# ADC_SarSol.net
KiCad netlist of a schematic drawn in Altium Designer
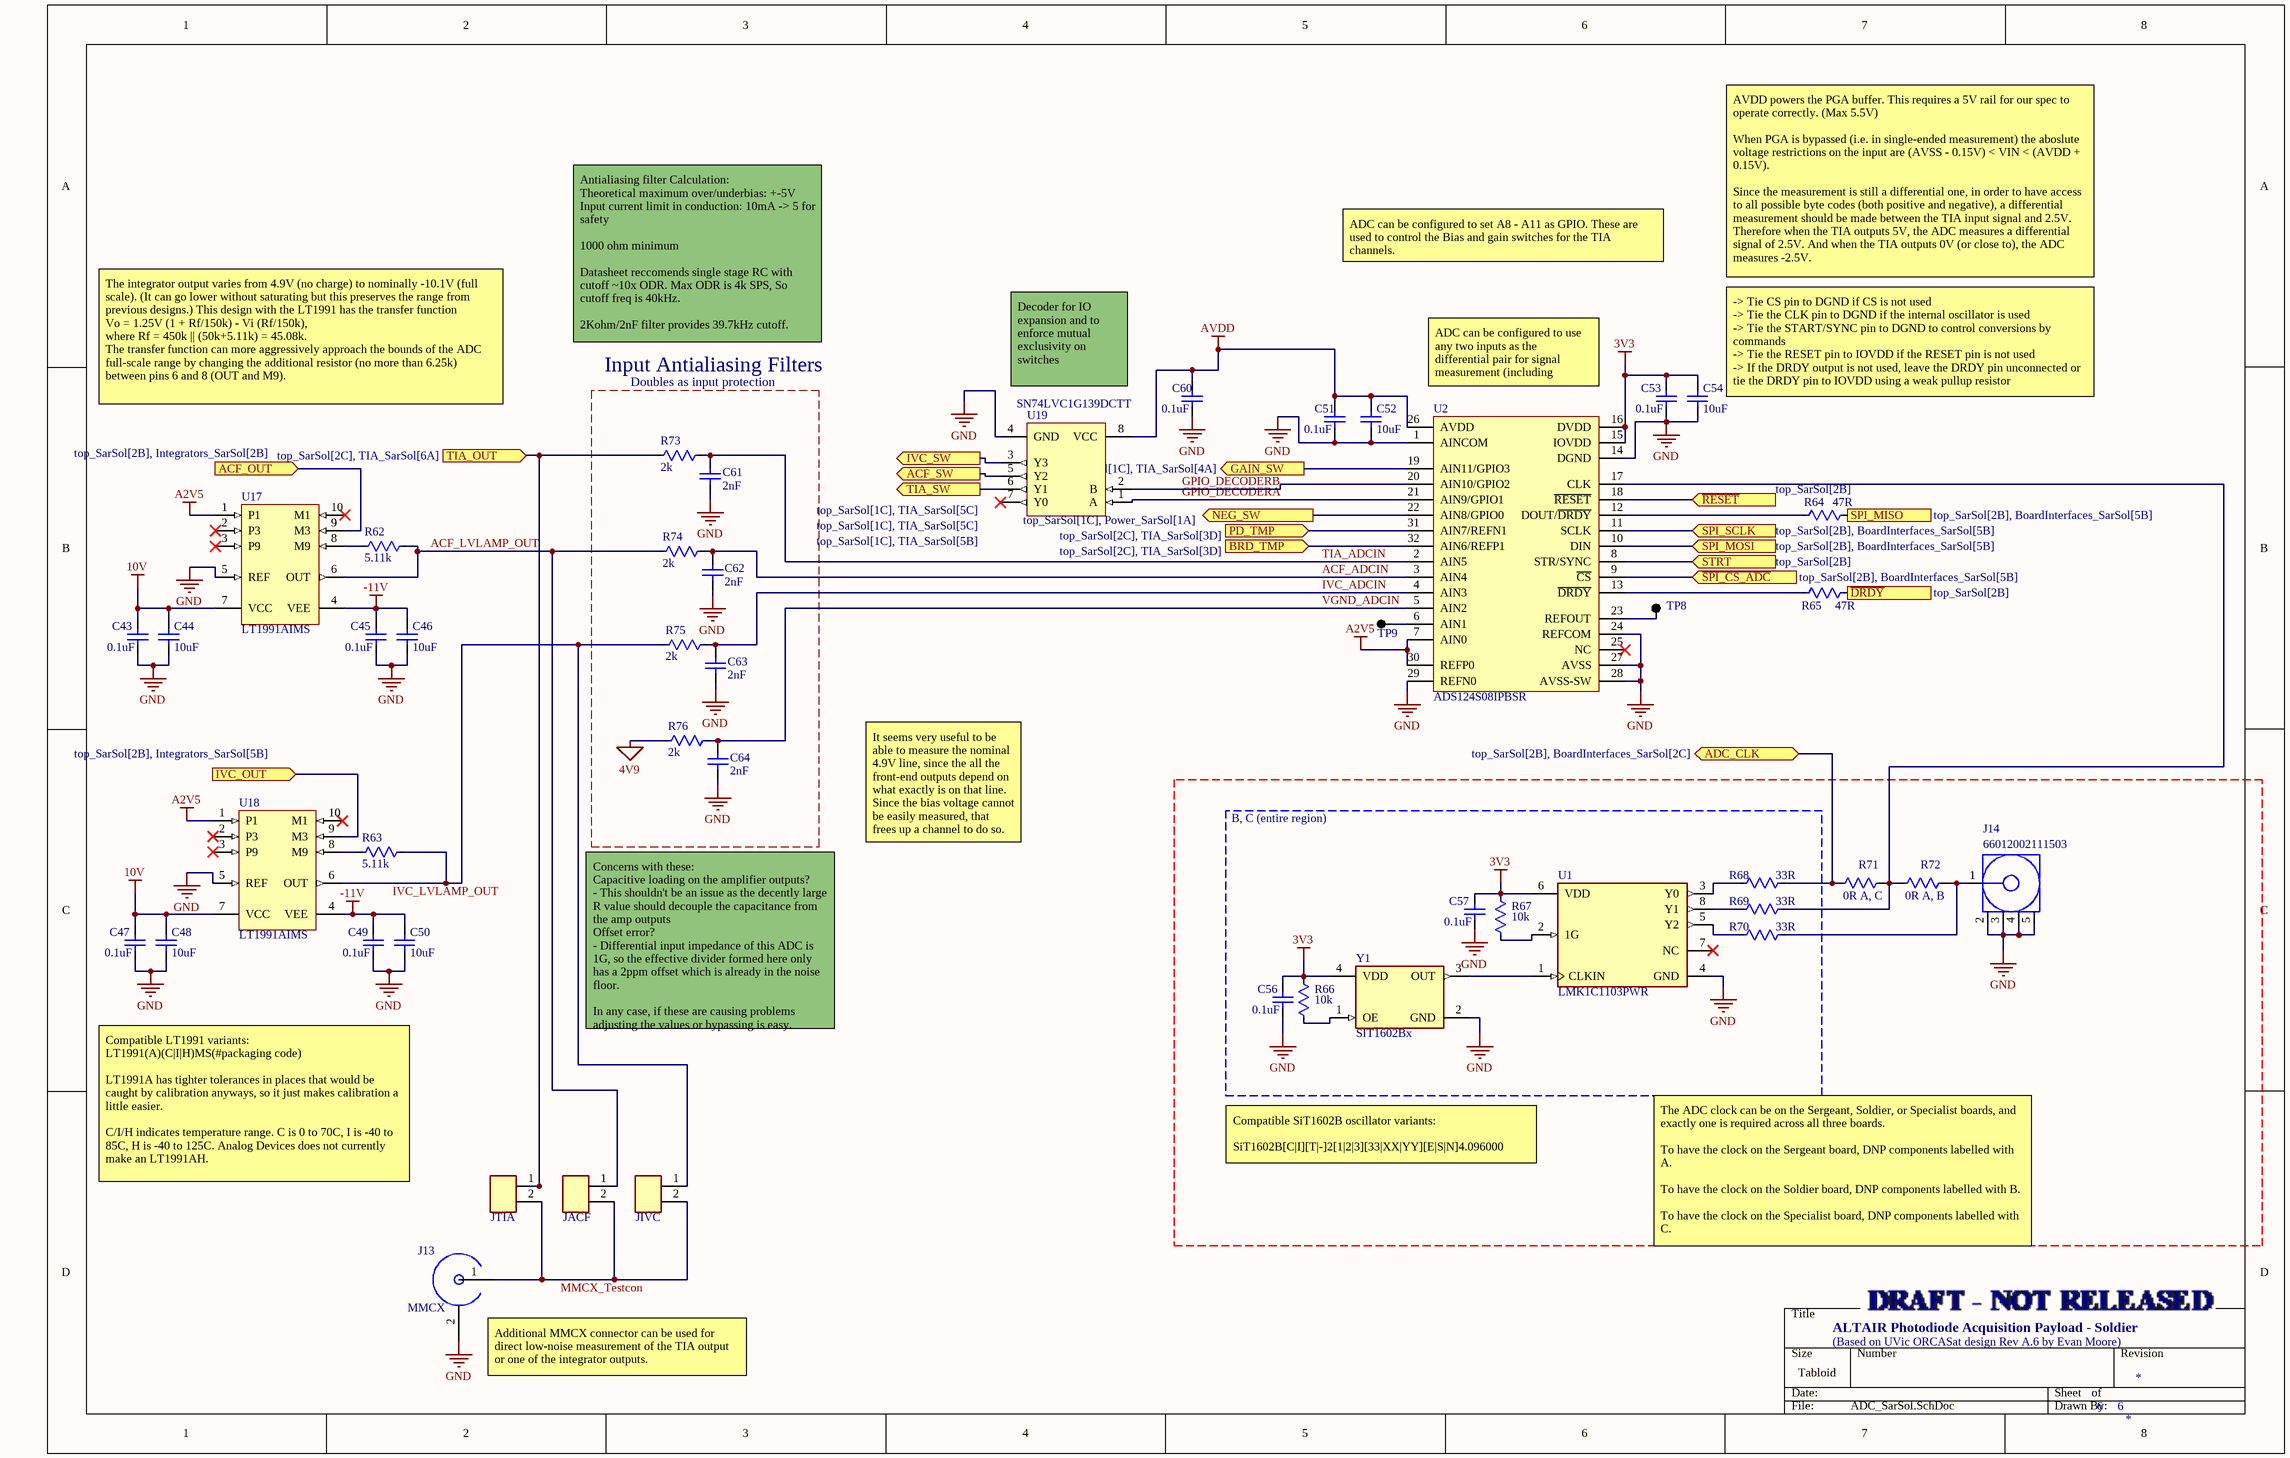
[diagram p0: ADC_SarSol.SchDoc]

(export (version "E")
  (design (tool "Eeschema 10.0.6"))
  (components
    (comp (ref "C43")
      (value "0.1uF")
      (footprint "CAP 0603 NON-IPC KEMET X7R")
      (description "Kemet C0603C104K5RACAUTO - Cap Ceramic 0.1uF 50V X7R 10% 0603 125C Paper T/R")
      (fields (field (name "MF") "Kemet") (field (name "MP") "C0603C104K5RACAUTO"))
      (libsource (lib "ALTAIR_PD_Capacitors") (part "CAP"))
    )
    (comp (ref "C44")
      (value "10uF")
      (footprint "CAP 0805 IPC MID DENSITY")
      (description "Murata GRM21BR61E106KA73L - Cap Ceramic 10uF 10% 25V X5R 0805")
      (fields (field (name "MF") "Murata") (field (name "MP") "GRM21BR61E106KA73L"))
      (libsource (lib "ALTAIR_PD_Capacitors") (part "CAP"))
    )
    (comp (ref "C45")
      (value "0.1uF")
      (footprint "CAP 0603 NON-IPC KEMET X7R")
      (description "Kemet C0603C104K5RACAUTO - Cap Ceramic 0.1uF 50V X7R 10% 0603 125C Paper T/R")
      (fields (field (name "MF") "Kemet") (field (name "MP") "C0603C104K5RACAUTO"))
      (libsource (lib "ALTAIR_PD_Capacitors") (part "CAP"))
    )
    (comp (ref "C46")
      (value "10uF")
      (footprint "CAP 0805 IPC MID DENSITY")
      (description "Murata GRM21BR61E106KA73L - Cap Ceramic 10uF 10% 25V X5R 0805")
      (fields (field (name "MF") "Murata") (field (name "MP") "GRM21BR61E106KA73L"))
      (libsource (lib "ALTAIR_PD_Capacitors") (part "CAP"))
    )
    (comp (ref "C47")
      (value "0.1uF")
      (footprint "CAP 0603 NON-IPC KEMET X7R")
      (description "Kemet C0603C104K5RACAUTO - Cap Ceramic 0.1uF 50V X7R 10% 0603 125C Paper T/R")
      (fields (field (name "MF") "Kemet") (field (name "MP") "C0603C104K5RACAUTO"))
      (libsource (lib "ALTAIR_PD_Capacitors") (part "CAP"))
    )
    (comp (ref "C48")
      (value "10uF")
      (footprint "CAP 0805 IPC MID DENSITY")
      (description "Murata GRM21BR61E106KA73L - Cap Ceramic 10uF 10% 25V X5R 0805")
      (fields (field (name "MF") "Murata") (field (name "MP") "GRM21BR61E106KA73L"))
      (libsource (lib "ALTAIR_PD_Capacitors") (part "CAP"))
    )
    (comp (ref "C49")
      (value "0.1uF")
      (footprint "CAP 0603 NON-IPC KEMET X7R")
      (description "Kemet C0603C104K5RACAUTO - Cap Ceramic 0.1uF 50V X7R 10% 0603 125C Paper T/R")
      (fields (field (name "MF") "Kemet") (field (name "MP") "C0603C104K5RACAUTO"))
      (libsource (lib "ALTAIR_PD_Capacitors") (part "CAP"))
    )
    (comp (ref "C50")
      (value "10uF")
      (footprint "CAP 0805 IPC MID DENSITY")
      (description "Murata GRM21BR61E106KA73L - Cap Ceramic 10uF 10% 25V X5R 0805")
      (fields (field (name "MF") "Murata") (field (name "MP") "GRM21BR61E106KA73L"))
      (libsource (lib "ALTAIR_PD_Capacitors") (part "CAP"))
    )
    (comp (ref "C51")
      (value "0.1uF")
      (footprint "CAP 0603 IPC MID DENSITY")
      (description "Kemet C0603C104K5RACAUTO - Cap Ceramic 0.1uF 50V X7R 10% 0603 125C Paper T/R")
      (fields (field (name "MF") "Kemet") (field (name "MP") "C0603C104K5RACAUTO"))
      (libsource (lib "ALTAIR_PD_Capacitors") (part "CAP"))
    )
    (comp (ref "C52")
      (value "10uF")
      (footprint "CAP 0805 IPC MID DENSITY")
      (description "Murata GRM21BR61E106KA73L - Cap Ceramic 10uF 10% 25V X5R 0805")
      (fields (field (name "MF") "Murata") (field (name "MP") "GRM21BR61E106KA73L"))
      (libsource (lib "ALTAIR_PD_Capacitors") (part "CAP"))
    )
    (comp (ref "C53")
      (value "0.1uF")
      (footprint "CAP 0603 IPC MID DENSITY")
      (description "Kemet C0603C104K5RACAUTO - Cap Ceramic 0.1uF 50V X7R 10% 0603 125C Paper T/R")
      (fields (field (name "MF") "Kemet") (field (name "MP") "C0603C104K5RACAUTO"))
      (libsource (lib "ALTAIR_PD_Capacitors") (part "CAP"))
    )
    (comp (ref "C54")
      (value "10uF")
      (footprint "CAP 0805 IPC MID DENSITY")
      (description "Murata GRM21BR61E106KA73L - Cap Ceramic 10uF 10% 25V X5R 0805")
      (fields (field (name "MF") "Murata") (field (name "MP") "GRM21BR61E106KA73L"))
      (libsource (lib "ALTAIR_PD_Capacitors") (part "CAP"))
    )
    (comp (ref "C56")
      (value "0.1uF")
      (footprint "CAP 0603 IPC MID DENSITY")
      (description "Kemet C0603C104K5RACAUTO - Cap Ceramic 0.1uF 50V X7R 10% 0603 125C Paper T/R")
      (fields (field (name "MF") "Kemet") (field (name "MP") "C0603C104K5RACAUTO"))
      (libsource (lib "ALTAIR_PD_Capacitors") (part "CAP"))
    )
    (comp (ref "C57")
      (value "0.1uF")
      (footprint "CAP 0603 IPC MID DENSITY")
      (description "Kemet C0603C104K5RACAUTO - Cap Ceramic 0.1uF 50V X7R 10% 0603 125C Paper T/R")
      (fields (field (name "MF") "Kemet") (field (name "MP") "C0603C104K5RACAUTO"))
      (libsource (lib "ALTAIR_PD_Capacitors") (part "CAP"))
    )
    (comp (ref "C60")
      (value "0.1uF")
      (footprint "CAP 0603 IPC MID DENSITY")
      (description "Kemet C0603C104K5RACAUTO - Cap Ceramic 0.1uF 50V X7R 10% 0603 125C Paper T/R")
      (fields (field (name "MF") "Kemet") (field (name "MP") "C0603C104K5RACAUTO"))
      (libsource (lib "ALTAIR_PD_Capacitors") (part "CAP"))
    )
    (comp (ref "C61")
      (value "2nF")
      (footprint "CAP 0603 IPC MID DENSITY")
      (description "Cap, Nonpolar, Any, Must choose footprint manually")
      (libsource (lib "ALTAIR_PD_Capacitors") (part "CAP"))
    )
    (comp (ref "C62")
      (value "2nF")
      (footprint "CAP 0603 IPC MID DENSITY")
      (description "Cap, Nonpolar, Any, Must choose footprint manually")
      (libsource (lib "ALTAIR_PD_Capacitors") (part "CAP"))
    )
    (comp (ref "C63")
      (value "2nF")
      (footprint "CAP 0603 IPC MID DENSITY")
      (description "Cap, Nonpolar, Any, Must choose footprint manually")
      (libsource (lib "ALTAIR_PD_Capacitors") (part "CAP"))
    )
    (comp (ref "C64")
      (value "2nF")
      (footprint "CAP 0603 IPC MID DENSITY")
      (description "Cap, Nonpolar, Any, Must choose footprint manually")
      (libsource (lib "ALTAIR_PD_Capacitors") (part "CAP"))
    )
    (comp (ref "J13")
      (value "MMCX")
      (footprint "COAX MMCX SMD")
      (description "Conn MMCX F 50Ohm Solder ST SMD Gold Tray")
      (fields (field (name "MF") "Molex") (field (name "MP") "0734152061"))
      (libsource (lib "ALTAIR_PD_Coaxial") (part "MMCX_recp"))
    )
    (comp (ref "J14")
      (value "66012002111503")
      (footprint "COAX MMCX THT")
      (description "Rf Coaxial, Mmcx Jack, 50 Ohm, Pcb Rohs Compliant: Yes ¦Wurth Elektronik 66012002111503")
      (fields (field (name "MF") "Wurth Elektronik"))
      (libsource (lib "ALTAIR_PD_Coaxial") (part "CMP-207975-000001-3"))
    )
    (comp (ref "JACF")
      (value "JACF")
      (footprint "ALTAIR_PD_Headers:JUMPER 2POS 1MM PITCH THT")
      (description "2x1 Header THT 1mm Pitch")
      (fields
        (field (name "MF") "GCT (GLOBAL CONNECTOR TECHNOLOGY)")
        (field (name "MP") "BC020-02-A-0200-0300-L-G")
      )
      (libsource (lib "ALTAIR_PD_Headers") (part "BC020-02-A-0200-0300-L-G"))
    )
    (comp (ref "JIVC")
      (value "JIVC")
      (footprint "ALTAIR_PD_Headers:JUMPER 2POS 1MM PITCH THT")
      (description "2x1 Header THT 1mm Pitch")
      (fields
        (field (name "MF") "GCT (GLOBAL CONNECTOR TECHNOLOGY)")
        (field (name "MP") "BC020-02-A-0200-0300-L-G")
      )
      (libsource (lib "ALTAIR_PD_Headers") (part "BC020-02-A-0200-0300-L-G"))
    )
    (comp (ref "JTIA")
      (value "JTIA")
      (footprint "ALTAIR_PD_Headers:JUMPER 2POS 1MM PITCH THT")
      (description "2x1 Header THT 1mm Pitch")
      (fields
        (field (name "MF") "GCT (GLOBAL CONNECTOR TECHNOLOGY)")
        (field (name "MP") "BC020-02-A-0200-0300-L-G")
      )
      (libsource (lib "ALTAIR_PD_Headers") (part "BC020-02-A-0200-0300-L-G"))
    )
    (comp (ref "R62")
      (value "5.11k")
      (footprint "RES 0402 IPC MID DENSITY")
      (description "Panasonic ERA-2AEB5111X - Res 5.11k 0.1% 1/16W SMD 0402")
      (fields (field (name "MF") "Panasonic Electronic Components") (field (name "MP") "ERA-2AEB5111X"))
      (libsource (lib "ALTAIR_PD_Resistors") (part "RES"))
    )
    (comp (ref "R63")
      (value "5.11k")
      (footprint "RES 0402 IPC MID DENSITY")
      (description "Panasonic ERA-2AEB5111X - Res 5.11k 0.1% 1/16W SMD 0402")
      (fields (field (name "MF") "Panasonic Electronic Components") (field (name "MP") "ERA-2AEB5111X"))
      (libsource (lib "ALTAIR_PD_Resistors") (part "RES"))
    )
    (comp (ref "R64")
      (value "47R")
      (footprint "RES 0402 NON-IPC SEI")
      (description "Stackpole RMCF0402JT47R0 - Res 47Ohm 5% 0.063W 0402 Thick Film AEC-Q200 compliant")
      (fields (field (name "MF") "Stackpole Electronics Inc.") (field (name "MP") "RMCF0402JT47R0"))
      (libsource (lib "ALTAIR_PD_Resistors") (part "RES"))
    )
    (comp (ref "R65")
      (value "47R")
      (footprint "RES 0402 NON-IPC SEI")
      (description "Stackpole RMCF0402JT47R0 - Res 47Ohm 5% 0.063W 0402 Thick Film AEC-Q200 compliant")
      (fields (field (name "MF") "Stackpole Electronics Inc.") (field (name "MP") "RMCF0402JT47R0"))
      (libsource (lib "ALTAIR_PD_Resistors") (part "RES"))
    )
    (comp (ref "R66")
      (value "10k")
      (footprint "RES 0603 IPC MID DENSITY")
      (description "Vishay CRCW060310K0FKEA SMD 0603 10k, CRCW e3 Series, 75V, thick film, 100mW")
      (fields (field (name "MF") "Vishay Dale") (field (name "MP") "CRCW060310K0FKEA"))
      (libsource (lib "ALTAIR_PD_Resistors") (part "RES"))
    )
    (comp (ref "R67")
      (value "10k")
      (footprint "RES 0603 IPC MID DENSITY")
      (description "Vishay CRCW060310K0FKEA SMD 0603 10k, CRCW e3 Series, 75V, thick film, 100mW")
      (fields (field (name "MF") "Vishay Dale") (field (name "MP") "CRCW060310K0FKEA"))
      (libsource (lib "ALTAIR_PD_Resistors") (part "RES"))
    )
    (comp (ref "R68")
      (value "33R")
      (footprint "RES 0402 NON-IPC YAGEO")
      (description "Yageo RC0402FR-0733RL - Res 33Ohm 1% 1/16W 0402")
      (fields (field (name "MF") "YAGEO") (field (name "MP") "RC0402FR-0733RL"))
      (libsource (lib "ALTAIR_PD_Resistors") (part "RES"))
    )
    (comp (ref "R69")
      (value "33R")
      (footprint "RES 0402 NON-IPC YAGEO")
      (description "Yageo RC0402FR-0733RL - Res 33Ohm 1% 1/16W 0402")
      (fields (field (name "MF") "YAGEO") (field (name "MP") "RC0402FR-0733RL"))
      (libsource (lib "ALTAIR_PD_Resistors") (part "RES"))
    )
    (comp (ref "R70")
      (value "33R")
      (footprint "RES 0402 NON-IPC YAGEO")
      (description "Yageo RC0402FR-0733RL - Res 33Ohm 1% 1/16W 0402")
      (fields (field (name "MF") "YAGEO") (field (name "MP") "RC0402FR-0733RL"))
      (libsource (lib "ALTAIR_PD_Resistors") (part "RES"))
    )
    (comp (ref "R71")
      (value "0R A, C")
      (footprint "RES 0402 IPC MID DENSITY")
      (description "Yageo RC0402JR-070RL - Res 0 Ohms 1/16W SMD 0402")
      (fields (field (name "MF") "YAGEO") (field (name "MP") "RC0402JR-070RL"))
      (libsource (lib "ALTAIR_PD_Resistors") (part "RES"))
    )
    (comp (ref "R72")
      (value "0R A, B")
      (footprint "RES 0402 IPC MID DENSITY")
      (description "Yageo RC0402JR-070RL - Res 0 Ohms 1/16W SMD 0402")
      (fields (field (name "MF") "YAGEO") (field (name "MP") "RC0402JR-070RL"))
      (libsource (lib "ALTAIR_PD_Resistors") (part "RES"))
    )
    (comp (ref "R73")
      (value "2k")
      (footprint "RES 0603 IPC MID DENSITY")
      (description "Res, Any, Manually select footprint")
      (libsource (lib "ALTAIR_PD_Resistors") (part "RES"))
    )
    (comp (ref "R74")
      (value "2k")
      (footprint "RES 0603 IPC MID DENSITY")
      (description "Res, Any, Manually select footprint")
      (libsource (lib "ALTAIR_PD_Resistors") (part "RES"))
    )
    (comp (ref "R75")
      (value "2k")
      (footprint "RES 0603 IPC MID DENSITY")
      (description "Res, Any, Manually select footprint")
      (libsource (lib "ALTAIR_PD_Resistors") (part "RES"))
    )
    (comp (ref "R76")
      (value "2k")
      (footprint "RES 0603 IPC MID DENSITY")
      (description "Res, Any, Manually select footprint")
      (libsource (lib "ALTAIR_PD_Resistors") (part "RES"))
    )
    (comp (ref "TP8")
      (value "Testpoint")
      (footprint "TESTPOINT THT")
      (libsource (lib "ALTAIR_PD_Testpoint") (part "Testpoint"))
    )
    (comp (ref "TP9")
      (value "Testpoint")
      (footprint "TESTPOINT THT")
      (libsource (lib "ALTAIR_PD_Testpoint") (part "Testpoint"))
    )
    (comp (ref "U1")
      (value "LMK1C1103PWR")
      (footprint "8-TSSOP 0.65MM PITCH 4.4MM WIDTH IPC MID DENSITY")
      (description "LVCMOS CLOCK BUFFER 3-CHANNEL")
      (fields (field (name "MF") "Texas Instruments"))
      (libsource (lib "ALTAIR_PD_ClockParts") (part "LMK1C1103PWR"))
    )
    (comp (ref "U2")
      (value "ADS124S08IPBSR")
      (footprint "32TQFP 7X7MM IPC LOW DENSITY")
      (description "24BIT ADC Delta-Sigma 4k samples/s PGA V-reference")
      (fields (field (name "MF") "Texas Instruments"))
      (libsource (lib "ALTAIR_PD_ADCs") (part "ADS124S08IPBSR"))
    )
    (comp (ref "U17")
      (value "LT1991AIMS")
      (footprint "10-SOP 0.5MM PITCH 3MM WIDTH IPC HIGH DENSITY")
      (fields
        (field (name "MF") "Linear Technology")
        (field (name "MP") "LT1991AIMS#PBF")
        (field (name "LINEAR TECHNOLOGY PART NUMBER") "LT1991")
      )
      (libsource (lib "ALTAIR_PD_Amplifiers") (part "LT1991IMS#TRPBF"))
    )
    (comp (ref "U18")
      (value "LT1991AIMS")
      (footprint "10-SOP 0.5MM PITCH 3MM WIDTH IPC HIGH DENSITY")
      (fields
        (field (name "MF") "Linear Technology")
        (field (name "MP") "LT1991AIMS#PBF")
        (field (name "LINEAR TECHNOLOGY PART NUMBER") "LT1991")
      )
      (libsource (lib "ALTAIR_PD_Amplifiers") (part "LT1991IMS#TRPBF"))
    )
    (comp (ref "U19")
      (value "SN74LVC1G139DCTT")
      (footprint "DCT0008A_L")
      (description "2-Line-to-4-Line Decoder, DCT0008A, SMALL T&R")
      (fields
        (field (name "MANUFACTURER") "Texas Instruments")
        (field (name "GENERIC PART NUMBER") "SN74LVC1G139")
      )
      (libsource (lib "Altium Content Vault") (part "TI-SN74LVC1G139-8"))
    )
    (comp (ref "Y1")
      (value "SIT1602Bx")
      (footprint "4PQFN NON-IPC SITIME")
      (description "MEMS OSC XO 4.096MHZ H/LVCMOS")
      (fields (field (name "MF") "SiTime") (field (name "MP") "SiT1602BC-21-XXN-4.096000"))
      (libsource (lib "ALTAIR_PD_ClockParts") (part "SIT1602Bx"))
    )
  )
  (nets
    (net (code "1") (name "-11V") (class "Default")
      (node (ref "C45") (pin "2") (pinfunction "2_2") (pintype "passive"))
      (node (ref "C46") (pin "2") (pinfunction "2_2") (pintype "passive"))
      (node (ref "C49") (pin "2") (pinfunction "2_2") (pintype "passive"))
      (node (ref "C50") (pin "2") (pinfunction "2_2") (pintype "passive"))
      (node (ref "U17") (pin "4") (pinfunction "VEE_4") (pintype "power_in"))
      (node (ref "U18") (pin "4") (pinfunction "VEE_4") (pintype "power_in"))
    )
    (net (code "2") (name "/ACF_ADCIN") (class "Default")
      (node (ref "C62") (pin "2") (pinfunction "2_2") (pintype "passive"))
      (node (ref "R74") (pin "2") (pinfunction "2_2") (pintype "passive"))
      (node (ref "U2") (pin "3") (pinfunction "AIN4_3") (pintype "passive"))
    )
    (net (code "3") (name "/ACF_LVLAMP_OUT") (class "Default")
      (node (ref "JACF") (pin "1") (pinfunction "1_1") (pintype "passive"))
      (node (ref "R62") (pin "2") (pinfunction "2_2") (pintype "passive"))
      (node (ref "R74") (pin "1") (pinfunction "1_1") (pintype "passive"))
      (node (ref "U17") (pin "6") (pinfunction "OUT_6") (pintype "output"))
    )
    (net (code "4") (name "/ACF_OUT") (class "Default")
      (node (ref "U17") (pin "9") (pinfunction "M3_9") (pintype "input"))
    )
    (net (code "5") (name "/ACF_SW") (class "Default")
      (node (ref "U19") (pin "5") (pinfunction "Y2_5") (pintype "output"))
    )
    (net (code "6") (name "/ADC_CLK") (class "Default")
      (node (ref "R68") (pin "1") (pinfunction "1_1") (pintype "passive"))
      (node (ref "R71") (pin "2") (pinfunction "2_2") (pintype "passive"))
    )
    (net (code "7") (name "/BRD_TMP") (class "Default")
      (node (ref "U2") (pin "32") (pinfunction "AIN6/REFP1_32") (pintype "passive"))
    )
    (net (code "8") (name "/DRDY") (class "Default")
      (node (ref "R65") (pin "2") (pinfunction "2_2") (pintype "passive"))
    )
    (net (code "9") (name "/GAIN_SW") (class "Default")
      (node (ref "U2") (pin "19") (pinfunction "AIN11/GPIO3_19") (pintype "passive"))
    )
    (net (code "10") (name "/GPIO_DECODERA") (class "Default")
      (node (ref "U19") (pin "1") (pinfunction "A_1") (pintype "input"))
      (node (ref "U2") (pin "21") (pinfunction "AIN9/GPIO1_21") (pintype "passive"))
    )
    (net (code "11") (name "/GPIO_DECODERB") (class "Default")
      (node (ref "U19") (pin "2") (pinfunction "B_2") (pintype "input"))
      (node (ref "U2") (pin "20") (pinfunction "AIN10/GPIO2_20") (pintype "passive"))
    )
    (net (code "12") (name "/IVC_ADCIN") (class "Default")
      (node (ref "C63") (pin "2") (pinfunction "2_2") (pintype "passive"))
      (node (ref "R75") (pin "2") (pinfunction "2_2") (pintype "passive"))
      (node (ref "U2") (pin "4") (pinfunction "AIN3_4") (pintype "passive"))
    )
    (net (code "13") (name "/IVC_LVLAMP_OUT") (class "Default")
      (node (ref "JIVC") (pin "1") (pinfunction "1_1") (pintype "passive"))
      (node (ref "R63") (pin "2") (pinfunction "2_2") (pintype "passive"))
      (node (ref "R75") (pin "1") (pinfunction "1_1") (pintype "passive"))
      (node (ref "U18") (pin "6") (pinfunction "OUT_6") (pintype "output"))
    )
    (net (code "14") (name "/IVC_OUT") (class "Default")
      (node (ref "U18") (pin "9") (pinfunction "M3_9") (pintype "input"))
    )
    (net (code "15") (name "/IVC_SW") (class "Default")
      (node (ref "U19") (pin "3") (pinfunction "Y3_3") (pintype "output"))
    )
    (net (code "16") (name "/MMCX_Testcon") (class "Default")
      (node (ref "J13") (pin "1") (pinfunction "1_1") (pintype "passive"))
      (node (ref "JACF") (pin "2") (pinfunction "2_2") (pintype "passive"))
      (node (ref "JIVC") (pin "2") (pinfunction "2_2") (pintype "passive"))
      (node (ref "JTIA") (pin "2") (pinfunction "2_2") (pintype "passive"))
    )
    (net (code "17") (name "/NEG_SW") (class "Default")
      (node (ref "U2") (pin "22") (pinfunction "AIN8/GPIO0_22") (pintype "passive"))
    )
    (net (code "18") (name "/PD_TMP") (class "Default")
      (node (ref "U2") (pin "31") (pinfunction "AIN7/REFN1_31") (pintype "passive"))
    )
    (net (code "19") (name "/RESET") (class "Default")
      (node (ref "U2") (pin "18") (pinfunction "~{RESET}_18") (pintype "passive"))
    )
    (net (code "20") (name "/SPI_CS_ADC") (class "Default")
      (node (ref "U2") (pin "9") (pinfunction "~{CS}_9") (pintype "passive"))
    )
    (net (code "21") (name "/SPI_MISO") (class "Default")
      (node (ref "R64") (pin "2") (pinfunction "2_2") (pintype "passive"))
    )
    (net (code "22") (name "/SPI_MOSI") (class "Default")
      (node (ref "U2") (pin "10") (pinfunction "DIN_10") (pintype "passive"))
    )
    (net (code "23") (name "/SPI_SCLK") (class "Default")
      (node (ref "U2") (pin "11") (pinfunction "SCLK_11") (pintype "passive"))
    )
    (net (code "24") (name "/STRT") (class "Default")
      (node (ref "U2") (pin "8") (pinfunction "STR/SYNC_8") (pintype "passive"))
    )
    (net (code "25") (name "/TIA_ADCIN") (class "Default")
      (node (ref "C61") (pin "2") (pinfunction "2_2") (pintype "passive"))
      (node (ref "R73") (pin "2") (pinfunction "2_2") (pintype "passive"))
      (node (ref "U2") (pin "2") (pinfunction "AIN5_2") (pintype "passive"))
    )
    (net (code "26") (name "/TIA_OUT") (class "Default")
      (node (ref "JTIA") (pin "1") (pinfunction "1_1") (pintype "passive"))
      (node (ref "R73") (pin "1") (pinfunction "1_1") (pintype "passive"))
    )
    (net (code "27") (name "/TIA_SW") (class "Default")
      (node (ref "U19") (pin "6") (pinfunction "Y1_6") (pintype "output"))
    )
    (net (code "28") (name "/VGND_ADCIN") (class "Default")
      (node (ref "C64") (pin "2") (pinfunction "2_2") (pintype "passive"))
      (node (ref "R76") (pin "2") (pinfunction "2_2") (pintype "passive"))
      (node (ref "U2") (pin "5") (pinfunction "AIN2_5") (pintype "passive"))
    )
    (net (code "29") (name "3V3") (class "Default")
      (node (ref "C53") (pin "2") (pinfunction "2_2") (pintype "passive"))
      (node (ref "C54") (pin "2") (pinfunction "2_2") (pintype "passive"))
      (node (ref "C56") (pin "2") (pinfunction "2_2") (pintype "passive"))
      (node (ref "C57") (pin "2") (pinfunction "2_2") (pintype "passive"))
      (node (ref "R66") (pin "2") (pinfunction "2_2") (pintype "passive"))
      (node (ref "R67") (pin "2") (pinfunction "2_2") (pintype "passive"))
      (node (ref "U1") (pin "6") (pinfunction "VDD_6") (pintype "power_in"))
      (node (ref "U2") (pin "15") (pinfunction "IOVDD_15") (pintype "passive"))
      (node (ref "U2") (pin "16") (pinfunction "DVDD_16") (pintype "passive"))
      (node (ref "Y1") (pin "4") (pinfunction "VDD_4") (pintype "power_in"))
    )
    (net (code "30") (name "4V9") (class "Default")
      (node (ref "R76") (pin "1") (pinfunction "1_1") (pintype "passive"))
    )
    (net (code "31") (name "10V") (class "Default")
      (node (ref "C43") (pin "2") (pinfunction "2_2") (pintype "passive"))
      (node (ref "C44") (pin "2") (pinfunction "2_2") (pintype "passive"))
      (node (ref "C47") (pin "2") (pinfunction "2_2") (pintype "passive"))
      (node (ref "C48") (pin "2") (pinfunction "2_2") (pintype "passive"))
      (node (ref "U17") (pin "7") (pinfunction "VCC_7") (pintype "power_in"))
      (node (ref "U18") (pin "7") (pinfunction "VCC_7") (pintype "power_in"))
    )
    (net (code "32") (name "A2V5") (class "Default")
      (node (ref "U17") (pin "1") (pinfunction "P1_1") (pintype "input"))
      (node (ref "U18") (pin "1") (pinfunction "P1_1") (pintype "input"))
      (node (ref "U2") (pin "30") (pinfunction "REFP0_30") (pintype "passive"))
      (node (ref "U2") (pin "7") (pinfunction "AIN0_7") (pintype "passive"))
    )
    (net (code "33") (name "AVDD") (class "Default")
      (node (ref "C51") (pin "2") (pinfunction "2_2") (pintype "passive"))
      (node (ref "C52") (pin "2") (pinfunction "2_2") (pintype "passive"))
      (node (ref "C60") (pin "2") (pinfunction "2_2") (pintype "passive"))
      (node (ref "U19") (pin "8") (pinfunction "VCC_8") (pintype "power_in"))
      (node (ref "U2") (pin "26") (pinfunction "AVDD_26") (pintype "passive"))
    )
    (net (code "34") (name "GND") (class "Default")
      (node (ref "C43") (pin "1") (pinfunction "1_1") (pintype "passive"))
      (node (ref "C44") (pin "1") (pinfunction "1_1") (pintype "passive"))
      (node (ref "C45") (pin "1") (pinfunction "1_1") (pintype "passive"))
      (node (ref "C46") (pin "1") (pinfunction "1_1") (pintype "passive"))
      (node (ref "C47") (pin "1") (pinfunction "1_1") (pintype "passive"))
      (node (ref "C48") (pin "1") (pinfunction "1_1") (pintype "passive"))
      (node (ref "C49") (pin "1") (pinfunction "1_1") (pintype "passive"))
      (node (ref "C50") (pin "1") (pinfunction "1_1") (pintype "passive"))
      (node (ref "C51") (pin "1") (pinfunction "1_1") (pintype "passive"))
      (node (ref "C52") (pin "1") (pinfunction "1_1") (pintype "passive"))
      (node (ref "C53") (pin "1") (pinfunction "1_1") (pintype "passive"))
      (node (ref "C54") (pin "1") (pinfunction "1_1") (pintype "passive"))
      (node (ref "C56") (pin "1") (pinfunction "1_1") (pintype "passive"))
      (node (ref "C57") (pin "1") (pinfunction "1_1") (pintype "passive"))
      (node (ref "C60") (pin "1") (pinfunction "1_1") (pintype "passive"))
      (node (ref "C61") (pin "1") (pinfunction "1_1") (pintype "passive"))
      (node (ref "C62") (pin "1") (pinfunction "1_1") (pintype "passive"))
      (node (ref "C63") (pin "1") (pinfunction "1_1") (pintype "passive"))
      (node (ref "C64") (pin "1") (pinfunction "1_1") (pintype "passive"))
      (node (ref "J13") (pin "2") (pinfunction "2_2") (pintype "passive"))
      (node (ref "J14") (pin "2") (pinfunction "GND_2") (pintype "passive"))
      (node (ref "J14") (pin "3") (pinfunction "GND_3") (pintype "passive"))
      (node (ref "J14") (pin "4") (pinfunction "GND_4") (pintype "passive"))
      (node (ref "J14") (pin "5") (pinfunction "GND_5") (pintype "passive"))
      (node (ref "U1") (pin "4") (pinfunction "GND_4") (pintype "power_in"))
      (node (ref "U17") (pin "5") (pinfunction "REF_5") (pintype "input"))
      (node (ref "U18") (pin "5") (pinfunction "REF_5") (pintype "input"))
      (node (ref "U19") (pin "4") (pinfunction "GND_4") (pintype "power_in"))
      (node (ref "U2") (pin "1") (pinfunction "AINCOM_1") (pintype "passive"))
      (node (ref "U2") (pin "14") (pinfunction "DGND_14") (pintype "passive"))
      (node (ref "U2") (pin "24") (pinfunction "REFCOM_24") (pintype "passive"))
      (node (ref "U2") (pin "27") (pinfunction "AVSS_27") (pintype "passive"))
      (node (ref "U2") (pin "28") (pinfunction "AVSS-SW_28") (pintype "passive"))
      (node (ref "U2") (pin "29") (pinfunction "REFN0_29") (pintype "passive"))
      (node (ref "Y1") (pin "2") (pinfunction "GND_2") (pintype "power_in"))
    )
    (net (code "35") (name "Net-(J14-Signal)") (class "Default")
      (node (ref "J14") (pin "1") (pinfunction "Signal_1") (pintype "passive"))
      (node (ref "R70") (pin "1") (pinfunction "1_1") (pintype "passive"))
      (node (ref "R72") (pin "1") (pinfunction "1_1") (pintype "passive"))
    )
    (net (code "36") (name "Net-(U1-1G)") (class "Default")
      (node (ref "R67") (pin "1") (pinfunction "1_1") (pintype "passive"))
      (node (ref "U1") (pin "2") (pinfunction "1G_2") (pintype "input"))
    )
    (net (code "37") (name "Net-(U1-CLKIN)") (class "Default")
      (node (ref "U1") (pin "1") (pinfunction "CLKIN_1") (pintype "input"))
      (node (ref "Y1") (pin "3") (pinfunction "OUT_3") (pintype "output"))
    )
    (net (code "38") (name "Net-(U1-Y0)") (class "Default")
      (node (ref "R68") (pin "2") (pinfunction "2_2") (pintype "passive"))
      (node (ref "U1") (pin "3") (pinfunction "Y0_3") (pintype "output"))
    )
    (net (code "39") (name "Net-(U1-Y1)") (class "Default")
      (node (ref "R69") (pin "2") (pinfunction "2_2") (pintype "passive"))
      (node (ref "U1") (pin "8") (pinfunction "Y1_8") (pintype "output"))
    )
    (net (code "40") (name "Net-(U1-Y2)") (class "Default")
      (node (ref "R70") (pin "2") (pinfunction "2_2") (pintype "passive"))
      (node (ref "U1") (pin "5") (pinfunction "Y2_5") (pintype "output"))
    )
    (net (code "41") (name "Net-(U2-AIN1)") (class "Default")
      (node (ref "TP9") (pin "1") (pinfunction "1_1") (pintype "passive"))
      (node (ref "U2") (pin "6") (pinfunction "AIN1_6") (pintype "passive"))
    )
    (net (code "42") (name "Net-(U2-CLK)") (class "Default")
      (node (ref "R69") (pin "1") (pinfunction "1_1") (pintype "passive"))
      (node (ref "R71") (pin "1") (pinfunction "1_1") (pintype "passive"))
      (node (ref "R72") (pin "2") (pinfunction "2_2") (pintype "passive"))
      (node (ref "U2") (pin "17") (pinfunction "CLK_17") (pintype "passive"))
    )
    (net (code "43") (name "Net-(U2-DOUT{slash}~{DRDY})") (class "Default")
      (node (ref "R64") (pin "1") (pinfunction "1_1") (pintype "passive"))
      (node (ref "U2") (pin "12") (pinfunction "DOUT/~{DRDY}_12") (pintype "passive"))
    )
    (net (code "44") (name "Net-(U2-REFOUT)") (class "Default")
      (node (ref "TP8") (pin "1") (pinfunction "1_1") (pintype "passive"))
      (node (ref "U2") (pin "23") (pinfunction "REFOUT_23") (pintype "passive"))
    )
    (net (code "45") (name "Net-(U2-~{DRDY})") (class "Default")
      (node (ref "R65") (pin "1") (pinfunction "1_1") (pintype "passive"))
      (node (ref "U2") (pin "13") (pinfunction "~{DRDY}_13") (pintype "passive"))
    )
    (net (code "46") (name "Net-(U17-M9)") (class "Default")
      (node (ref "R62") (pin "1") (pinfunction "1_1") (pintype "passive"))
      (node (ref "U17") (pin "8") (pinfunction "M9_8") (pintype "input"))
    )
    (net (code "47") (name "Net-(U18-M9)") (class "Default")
      (node (ref "R63") (pin "1") (pinfunction "1_1") (pintype "passive"))
      (node (ref "U18") (pin "8") (pinfunction "M9_8") (pintype "input"))
    )
    (net (code "48") (name "Net-(Y1-OE)") (class "Default")
      (node (ref "R66") (pin "1") (pinfunction "1_1") (pintype "passive"))
      (node (ref "Y1") (pin "1") (pinfunction "OE_1") (pintype "input"))
    )
    (net (code "49") (name "unconnected-(U1-NC-Pad7)") (class "Default")
      (node (ref "U1") (pin "7") (pinfunction "NC_7") (pintype "passive+no_connect"))
    )
    (net (code "50") (name "unconnected-(U2-NC-Pad25)") (class "Default")
      (node (ref "U2") (pin "25") (pinfunction "NC_25") (pintype "passive+no_connect"))
    )
    (net (code "51") (name "unconnected-(U17-M1-Pad10)") (class "Default")
      (node (ref "U17") (pin "10") (pinfunction "M1_10") (pintype "input+no_connect"))
    )
    (net (code "52") (name "unconnected-(U17-P3-Pad2)") (class "Default")
      (node (ref "U17") (pin "2") (pinfunction "P3_2") (pintype "input+no_connect"))
    )
    (net (code "53") (name "unconnected-(U17-P9-Pad3)") (class "Default")
      (node (ref "U17") (pin "3") (pinfunction "P9_3") (pintype "input+no_connect"))
    )
    (net (code "54") (name "unconnected-(U18-M1-Pad10)") (class "Default")
      (node (ref "U18") (pin "10") (pinfunction "M1_10") (pintype "input+no_connect"))
    )
    (net (code "55") (name "unconnected-(U18-P3-Pad2)") (class "Default")
      (node (ref "U18") (pin "2") (pinfunction "P3_2") (pintype "input+no_connect"))
    )
    (net (code "56") (name "unconnected-(U18-P9-Pad3)") (class "Default")
      (node (ref "U18") (pin "3") (pinfunction "P9_3") (pintype "input+no_connect"))
    )
    (net (code "57") (name "unconnected-(U19-Y0-Pad7)") (class "Default")
      (node (ref "U19") (pin "7") (pinfunction "Y0_7") (pintype "output+no_connect"))
    )
  )
)
